# PPSB-T.net
KiCad netlist of a schematic drawn in EAGLE
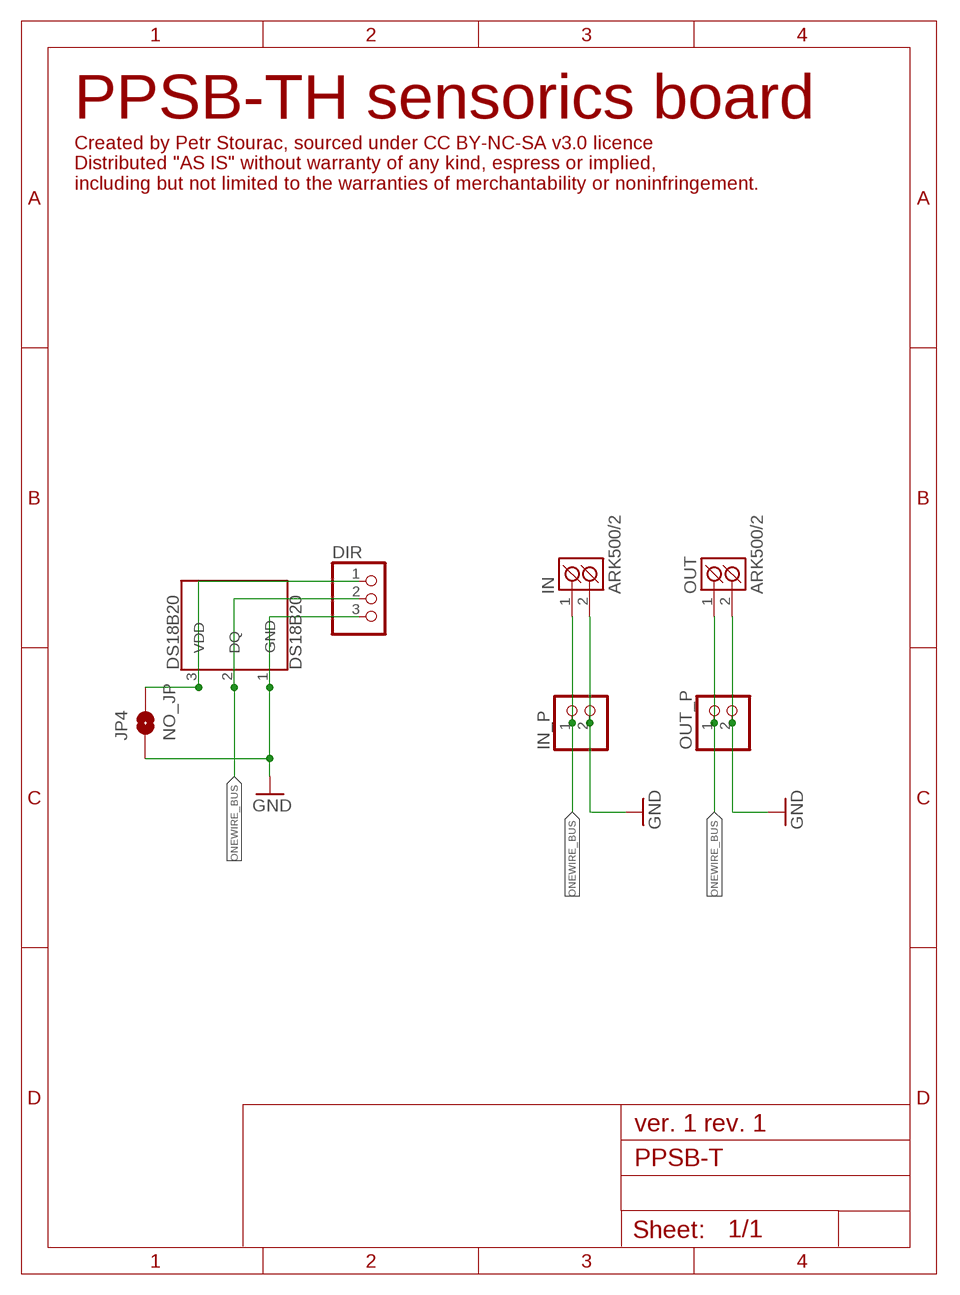
[diagram p0: schematic, sheet 1]

(export (version "E")
  (design (tool "Eeschema 10.0.6"))
  (components
    (comp (ref "DIR")
      (value "PINHD-1X3")
      (footprint "eagle-import:1X03")
      (libsource (lib "eagle-import") (part "PINHD-1X3"))
    )
    (comp (ref "DS18B20")
      (value "DS18B20")
      (footprint "eagle-import:TO-92-AMMO")
      (libsource (lib "eagle-import") (part "DS18B20"))
    )
    (comp (ref "IN")
      (value "ARK500/2")
      (footprint "eagle-import:ARK500_2")
      (libsource (lib "eagle-import") (part "ARK500/2"))
    )
    (comp (ref "IN_P")
      (value "PINHD-1X2")
      (footprint "eagle-import:1X02")
      (libsource (lib "eagle-import") (part "PINHD-1X2"))
    )
    (comp (ref "JP4")
      (value "NO_JP")
      (footprint "eagle-import:SMT-JUMPER_2_NO_NO-SILK")
      (libsource (lib "eagle-import") (part "JUMPER-SMT_2_NO_NO-SILK"))
    )
    (comp (ref "OUT")
      (value "ARK500/2")
      (footprint "eagle-import:ARK500_2")
      (libsource (lib "eagle-import") (part "ARK500/2"))
    )
    (comp (ref "OUT_P")
      (value "PINHD-1X2")
      (footprint "eagle-import:1X02")
      (libsource (lib "eagle-import") (part "PINHD-1X2"))
    )
  )
  (nets
    (net (code "1") (name "GND") (class "Default")
      (node (ref "DIR") (pin "3") (pinfunction "3_3") (pintype "passive"))
      (node (ref "DS18B20") (pin "1") (pinfunction "GND_1") (pintype "power_in"))
      (node (ref "IN") (pin "2") (pinfunction "K2_2") (pintype "passive"))
      (node (ref "IN_P") (pin "2") (pinfunction "2_2") (pintype "passive"))
      (node (ref "JP4") (pin "1") (pinfunction "1_1") (pintype "passive"))
      (node (ref "OUT") (pin "2") (pinfunction "K2_2") (pintype "passive"))
      (node (ref "OUT_P") (pin "2") (pinfunction "2_2") (pintype "passive"))
    )
    (net (code "2") (name "Net-(DS18B20-VDD)") (class "Default")
      (node (ref "DIR") (pin "1") (pinfunction "1_1") (pintype "passive"))
      (node (ref "DS18B20") (pin "3") (pinfunction "VDD_3") (pintype "power_in"))
      (node (ref "JP4") (pin "2") (pinfunction "2_2") (pintype "passive"))
    )
    (net (code "3") (name "ONEWIRE_BUS") (class "Default")
      (node (ref "DIR") (pin "2") (pinfunction "2_2") (pintype "passive"))
      (node (ref "DS18B20") (pin "2") (pinfunction "DQ_2") (pintype "bidirectional"))
      (node (ref "IN") (pin "1") (pinfunction "K1_1") (pintype "passive"))
      (node (ref "IN_P") (pin "1") (pinfunction "1_1") (pintype "passive"))
      (node (ref "OUT") (pin "1") (pinfunction "K1_1") (pintype "passive"))
      (node (ref "OUT_P") (pin "1") (pinfunction "1_1") (pintype "passive"))
    )
  )
)
